# Main.net
KiCad netlist of a schematic drawn in Altium Designer
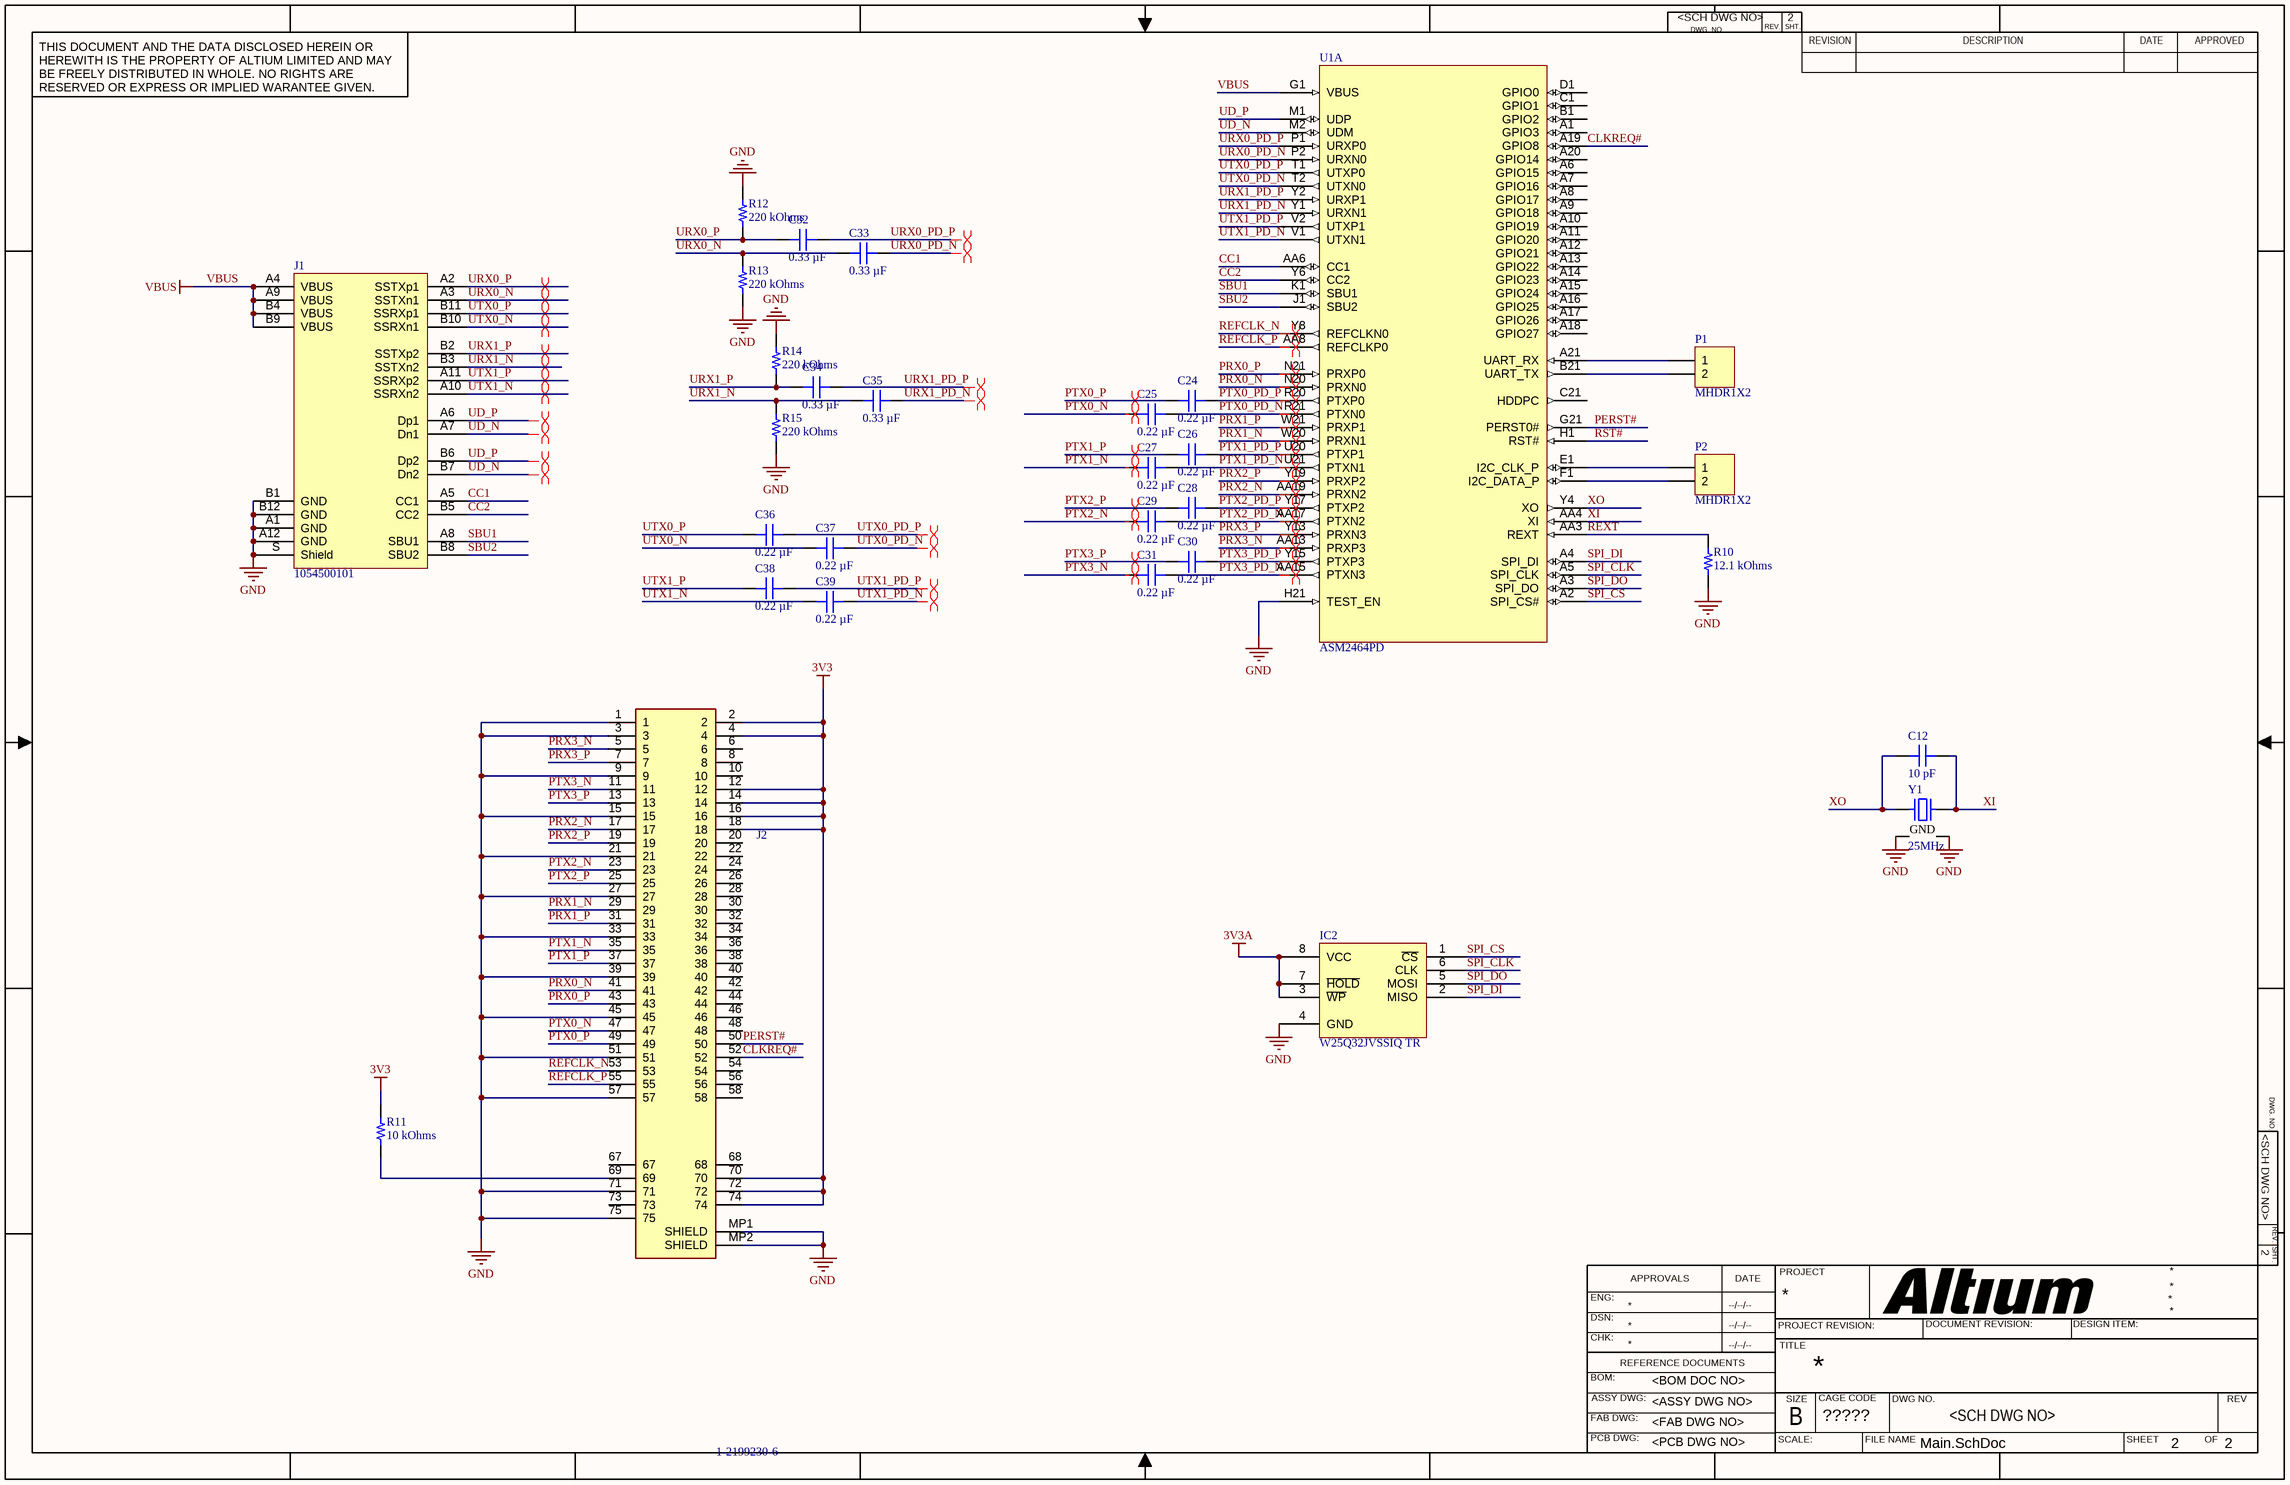
[diagram p0: Main.SchDoc]

(export (version "E")
  (design (tool "Eeschema 10.0.6"))
  (components
    (comp (ref "C12")
      (value "10 pF")
      (footprint "CAP 0603_1608")
      (description "CAP CER 10PF 200V C0G/NPO 0603")
      (fields (field (name "PART NUMBER") "CC0603JRNPOABN100") (field (name "MANUFACTURER") "Yageo"))
      (libsource (lib "Celestial Altium Library - altium_library") (part "Capacitor"))
    )
    (comp (ref "C24")
      (value "0.22 µF")
      (footprint "CAP 0402_1005")
      (description "CAP CER 0.22UF 35V X6S 0402")
      (fields
        (field (name "PART NUMBER") "GRM155C8YA224KE01J")
        (field (name "MANUFACTURER") "Murata Electronics")
      )
      (libsource (lib "Celestial Altium Library - altium_library") (part "Capacitor"))
    )
    (comp (ref "C25")
      (value "0.22 µF")
      (footprint "CAP 0402_1005")
      (description "CAP CER 0.22UF 35V X6S 0402")
      (fields
        (field (name "PART NUMBER") "GRM155C8YA224KE01J")
        (field (name "MANUFACTURER") "Murata Electronics")
      )
      (libsource (lib "Celestial Altium Library - altium_library") (part "Capacitor"))
    )
    (comp (ref "C26")
      (value "0.22 µF")
      (footprint "CAP 0402_1005")
      (description "CAP CER 0.22UF 35V X6S 0402")
      (fields
        (field (name "PART NUMBER") "GRM155C8YA224KE01J")
        (field (name "MANUFACTURER") "Murata Electronics")
      )
      (libsource (lib "Celestial Altium Library - altium_library") (part "Capacitor"))
    )
    (comp (ref "C27")
      (value "0.22 µF")
      (footprint "CAP 0402_1005")
      (description "CAP CER 0.22UF 35V X6S 0402")
      (fields
        (field (name "PART NUMBER") "GRM155C8YA224KE01J")
        (field (name "MANUFACTURER") "Murata Electronics")
      )
      (libsource (lib "Celestial Altium Library - altium_library") (part "Capacitor"))
    )
    (comp (ref "C28")
      (value "0.22 µF")
      (footprint "CAP 0402_1005")
      (description "CAP CER 0.22UF 35V X6S 0402")
      (fields
        (field (name "PART NUMBER") "GRM155C8YA224KE01J")
        (field (name "MANUFACTURER") "Murata Electronics")
      )
      (libsource (lib "Celestial Altium Library - altium_library") (part "Capacitor"))
    )
    (comp (ref "C29")
      (value "0.22 µF")
      (footprint "CAP 0402_1005")
      (description "CAP CER 0.22UF 35V X6S 0402")
      (fields
        (field (name "PART NUMBER") "GRM155C8YA224KE01J")
        (field (name "MANUFACTURER") "Murata Electronics")
      )
      (libsource (lib "Celestial Altium Library - altium_library") (part "Capacitor"))
    )
    (comp (ref "C30")
      (value "0.22 µF")
      (footprint "CAP 0402_1005")
      (description "CAP CER 0.22UF 35V X6S 0402")
      (fields
        (field (name "PART NUMBER") "GRM155C8YA224KE01J")
        (field (name "MANUFACTURER") "Murata Electronics")
      )
      (libsource (lib "Celestial Altium Library - altium_library") (part "Capacitor"))
    )
    (comp (ref "C31")
      (value "0.22 µF")
      (footprint "CAP 0402_1005")
      (description "CAP CER 0.22UF 35V X6S 0402")
      (fields
        (field (name "PART NUMBER") "GRM155C8YA224KE01J")
        (field (name "MANUFACTURER") "Murata Electronics")
      )
      (libsource (lib "Celestial Altium Library - altium_library") (part "Capacitor"))
    )
    (comp (ref "C32")
      (value "0.33 µF")
      (footprint "CAP 0201_0603")
      (description "CAP CER 0.33UF 6.3V X5R 0201")
      (fields
        (field (name "PART NUMBER") "GRM033R60J334ME90D")
        (field (name "MANUFACTURER") "Murata Electronics")
      )
      (libsource (lib "Celestial Altium Library - altium_library") (part "Capacitor"))
    )
    (comp (ref "C33")
      (value "0.33 µF")
      (footprint "CAP 0201_0603")
      (description "CAP CER 0.33UF 6.3V X5R 0201")
      (fields
        (field (name "PART NUMBER") "GRM033R60J334ME90D")
        (field (name "MANUFACTURER") "Murata Electronics")
      )
      (libsource (lib "Celestial Altium Library - altium_library") (part "Capacitor"))
    )
    (comp (ref "C34")
      (value "0.33 µF")
      (footprint "CAP 0201_0603")
      (description "CAP CER 0.33UF 6.3V X5R 0201")
      (fields
        (field (name "PART NUMBER") "GRM033R60J334ME90D")
        (field (name "MANUFACTURER") "Murata Electronics")
      )
      (libsource (lib "Celestial Altium Library - altium_library") (part "Capacitor"))
    )
    (comp (ref "C35")
      (value "0.33 µF")
      (footprint "CAP 0201_0603")
      (description "CAP CER 0.33UF 6.3V X5R 0201")
      (fields
        (field (name "PART NUMBER") "GRM033R60J334ME90D")
        (field (name "MANUFACTURER") "Murata Electronics")
      )
      (libsource (lib "Celestial Altium Library - altium_library") (part "Capacitor"))
    )
    (comp (ref "C36")
      (value "0.22 µF")
      (footprint "CAP 0201_0603")
      (description "CAP CER 0.22UF 25V X5R 0201")
      (fields
        (field (name "PART NUMBER") "GRM033R61E224KE01J")
        (field (name "MANUFACTURER") "Murata Electronics")
      )
      (libsource (lib "Celestial Altium Library - altium_library") (part "Capacitor"))
    )
    (comp (ref "C37")
      (value "0.22 µF")
      (footprint "CAP 0201_0603")
      (description "CAP CER 0.22UF 25V X5R 0201")
      (fields
        (field (name "PART NUMBER") "GRM033R61E224KE01J")
        (field (name "MANUFACTURER") "Murata Electronics")
      )
      (libsource (lib "Celestial Altium Library - altium_library") (part "Capacitor"))
    )
    (comp (ref "C38")
      (value "0.22 µF")
      (footprint "CAP 0201_0603")
      (description "CAP CER 0.22UF 25V X5R 0201")
      (fields
        (field (name "PART NUMBER") "GRM033R61E224KE01J")
        (field (name "MANUFACTURER") "Murata Electronics")
      )
      (libsource (lib "Celestial Altium Library - altium_library") (part "Capacitor"))
    )
    (comp (ref "C39")
      (value "0.22 µF")
      (footprint "CAP 0201_0603")
      (description "CAP CER 0.22UF 25V X5R 0201")
      (fields
        (field (name "PART NUMBER") "GRM033R61E224KE01J")
        (field (name "MANUFACTURER") "Murata Electronics")
      )
      (libsource (lib "Celestial Altium Library - altium_library") (part "Capacitor"))
    )
    (comp (ref "IC2")
      (value "W25Q32JVSSIQ TR")
      (footprint "WINBOND SOIC-8 208MIL WIDE")
      (description "IC FLASH 32M SPI 133MHZ 8SOIC")
      (fields (field (name "MANUFACTURER") "Winbond Electronics"))
      (libsource (lib "Celestial Altium Library - altium_library") (part "WINBOND FLASH SPI 8PIN"))
    )
    (comp (ref "J1")
      (value "1054500101")
      (footprint "Molex 1054500101")
      (description "CONN RCP USB3.1 TYPEC 24P SMD RA")
      (fields (field (name "MANUFACTURER") "Molex"))
      (libsource (lib "Celestial Altium Library - altium_library") (part "USB 3.0 Type C"))
    )
    (comp (ref "J2")
      (value "1-2199230-6")
      (footprint "121992306")
      (description "M.2 0.5PITCH 4.2H KEY M 30U AU")
      (fields (field (name "MF") "TE Connectivity") (field (name "DIGI-KEY_PART_NUMBER") "A118046TR-ND"))
      (libsource (lib "1-2199230-6") (part "1-2199230-6"))
    )
    (comp (ref "P1")
      (value "MHDR1X2")
      (footprint "MHDR1X2")
      (description "Header, 2-Pin")
      (fields (field (name "PUBLISHER") "Altium Limited"))
      (libsource (lib "Miscellaneous Connectors") (part "MHDR1X2"))
    )
    (comp (ref "P2")
      (value "MHDR1X2")
      (footprint "MHDR1X2")
      (description "Header, 2-Pin")
      (fields (field (name "PUBLISHER") "Altium Limited"))
      (libsource (lib "Miscellaneous Connectors") (part "MHDR1X2"))
    )
    (comp (ref "R10")
      (value "12.1 kOhms")
      (footprint "RES 0603_1608")
      (description "RES 12.1K OHM 0.1% 1/16W 0603")
      (fields
        (field (name "PART NUMBER") "RNCS0603BKE12K1")
        (field (name "MANUFACTURER") "Stackpole Electronics Inc")
      )
      (libsource (lib "Celestial Altium Library - altium_library") (part "Resistor"))
    )
    (comp (ref "R11")
      (value "10 kOhms")
      (footprint "RES 0805_2012")
      (description "RES SMD 10K OHM 1% 1/8W 0805")
      (fields (field (name "PART NUMBER") "CR0805-FX-1002ELF") (field (name "MANUFACTURER") "Bourns Inc."))
      (libsource (lib "Celestial Altium Library - altium_library") (part "Resistor"))
    )
    (comp (ref "R12")
      (value "220 kOhms")
      (footprint "RES 0201_0603")
      (description "RES SMD 220K OHM 1% 1/20W 0201")
      (fields
        (field (name "PART NUMBER") "ERJ-1GNF2203C")
        (field (name "MANUFACTURER") "Panasonic Electronic Components")
      )
      (libsource (lib "Celestial Altium Library - altium_library") (part "Resistor"))
    )
    (comp (ref "R13")
      (value "220 kOhms")
      (footprint "RES 0201_0603")
      (description "RES SMD 220K OHM 1% 1/20W 0201")
      (fields
        (field (name "PART NUMBER") "ERJ-1GNF2203C")
        (field (name "MANUFACTURER") "Panasonic Electronic Components")
      )
      (libsource (lib "Celestial Altium Library - altium_library") (part "Resistor"))
    )
    (comp (ref "R14")
      (value "220 kOhms")
      (footprint "RES 0201_0603")
      (description "RES SMD 220K OHM 1% 1/20W 0201")
      (fields
        (field (name "PART NUMBER") "ERJ-1GNF2203C")
        (field (name "MANUFACTURER") "Panasonic Electronic Components")
      )
      (libsource (lib "Celestial Altium Library - altium_library") (part "Resistor"))
    )
    (comp (ref "R15")
      (value "220 kOhms")
      (footprint "RES 0201_0603")
      (description "RES SMD 220K OHM 1% 1/20W 0201")
      (fields
        (field (name "PART NUMBER") "ERJ-1GNF2203C")
        (field (name "MANUFACTURER") "Panasonic Electronic Components")
      )
      (libsource (lib "Celestial Altium Library - altium_library") (part "Resistor"))
    )
    (comp (ref "U1")
      (value "ASM2464PD")
      (footprint "BGA273C46P21X21_1000X1000X98_2")
      (libsource (lib " JS") (part "ASM2464PD"))
    )
    (comp (ref "Y1")
      (value "25MHz")
      (footprint "ABRACON ABM8G")
      (description "CRYSTAL 25.0000MHZ 18PF SMD")
      (fields
        (field (name "PART NUMBER") "ABM8G-25.000MHZ-18-D2Y-T")
        (field (name "MANUFACTURER") "Abracon LLC")
      )
      (libsource (lib "Celestial Altium Library - altium_library") (part "Abracon Crystal ABM8G"))
    )
  )
  (nets
    (net (code "1") (name "/CC1") (class "Default")
      (node (ref "J1") (pin "A5") (pinfunction "CC1_A5") (pintype "passive"))
      (node (ref "U1") (pin "AA6") (pinfunction "CC1_AA6") (pintype "bidirectional"))
    )
    (net (code "2") (name "/CC2") (class "Default")
      (node (ref "J1") (pin "B5") (pinfunction "CC2_B5") (pintype "passive"))
      (node (ref "U1") (pin "Y6") (pinfunction "CC2_Y6") (pintype "bidirectional"))
    )
    (net (code "3") (name "/CLKREQ#") (class "Default")
      (node (ref "J2") (pin "52") (pinfunction "52_52") (pintype "passive"))
      (node (ref "U1") (pin "A19") (pinfunction "GPIO8_A19") (pintype "bidirectional"))
    )
    (net (code "4") (name "/PERST#") (class "Default")
      (node (ref "J2") (pin "50") (pinfunction "50_50") (pintype "passive"))
      (node (ref "U1") (pin "G21") (pinfunction "PERST0#_G21") (pintype "output"))
    )
    (net (code "5") (name "/PRX0_N") (class "Default")
      (node (ref "J2") (pin "41") (pinfunction "41_41") (pintype "passive"))
      (node (ref "U1") (pin "N20") (pinfunction "PRXN0_N20") (pintype "input"))
    )
    (net (code "6") (name "/PRX0_P") (class "Default")
      (node (ref "J2") (pin "43") (pinfunction "43_43") (pintype "passive"))
      (node (ref "U1") (pin "N21") (pinfunction "PRXP0_N21") (pintype "input"))
    )
    (net (code "7") (name "/PRX1_N") (class "Default")
      (node (ref "J2") (pin "29") (pinfunction "29_29") (pintype "passive"))
      (node (ref "U1") (pin "W20") (pinfunction "PRXN1_W20") (pintype "input"))
    )
    (net (code "8") (name "/PRX1_P") (class "Default")
      (node (ref "J2") (pin "31") (pinfunction "31_31") (pintype "passive"))
      (node (ref "U1") (pin "W21") (pinfunction "PRXP1_W21") (pintype "input"))
    )
    (net (code "9") (name "/PRX2_N") (class "Default")
      (node (ref "J2") (pin "17") (pinfunction "17_17") (pintype "passive"))
      (node (ref "U1") (pin "AA19") (pinfunction "PRXN2_AA19") (pintype "input"))
    )
    (net (code "10") (name "/PRX2_P") (class "Default")
      (node (ref "J2") (pin "19") (pinfunction "19_19") (pintype "passive"))
      (node (ref "U1") (pin "Y19") (pinfunction "PRXP2_Y19") (pintype "input"))
    )
    (net (code "11") (name "/PRX3_N") (class "Default")
      (node (ref "J2") (pin "5") (pinfunction "5_5") (pintype "passive"))
      (node (ref "U1") (pin "AA13") (pinfunction "PRXP3_AA13") (pintype "input"))
    )
    (net (code "12") (name "/PRX3_P") (class "Default")
      (node (ref "J2") (pin "7") (pinfunction "7_7") (pintype "passive"))
      (node (ref "U1") (pin "Y13") (pinfunction "PRXN3_Y13") (pintype "input"))
    )
    (net (code "13") (name "/PTX0_N") (class "Default")
      (node (ref "C25") (pin "1") (pinfunction "1_1") (pintype "passive"))
      (node (ref "J2") (pin "47") (pinfunction "47_47") (pintype "passive"))
    )
    (net (code "14") (name "/PTX0_P") (class "Default")
      (node (ref "C24") (pin "1") (pinfunction "1_1") (pintype "passive"))
      (node (ref "J2") (pin "49") (pinfunction "49_49") (pintype "passive"))
    )
    (net (code "15") (name "/PTX0_PD_N") (class "Default")
      (node (ref "C25") (pin "2") (pinfunction "2_2") (pintype "passive"))
      (node (ref "U1") (pin "R21") (pinfunction "PTXN0_R21") (pintype "output"))
    )
    (net (code "16") (name "/PTX0_PD_P") (class "Default")
      (node (ref "C24") (pin "2") (pinfunction "2_2") (pintype "passive"))
      (node (ref "U1") (pin "R20") (pinfunction "PTXP0_R20") (pintype "output"))
    )
    (net (code "17") (name "/PTX1_N") (class "Default")
      (node (ref "C27") (pin "1") (pinfunction "1_1") (pintype "passive"))
      (node (ref "J2") (pin "35") (pinfunction "35_35") (pintype "passive"))
    )
    (net (code "18") (name "/PTX1_P") (class "Default")
      (node (ref "C26") (pin "1") (pinfunction "1_1") (pintype "passive"))
      (node (ref "J2") (pin "37") (pinfunction "37_37") (pintype "passive"))
    )
    (net (code "19") (name "/PTX1_PD_N") (class "Default")
      (node (ref "C27") (pin "2") (pinfunction "2_2") (pintype "passive"))
      (node (ref "U1") (pin "U21") (pinfunction "PTXN1_U21") (pintype "output"))
    )
    (net (code "20") (name "/PTX1_PD_P") (class "Default")
      (node (ref "C26") (pin "2") (pinfunction "2_2") (pintype "passive"))
      (node (ref "U1") (pin "U20") (pinfunction "PTXP1_U20") (pintype "output"))
    )
    (net (code "21") (name "/PTX2_N") (class "Default")
      (node (ref "C29") (pin "1") (pinfunction "1_1") (pintype "passive"))
      (node (ref "J2") (pin "23") (pinfunction "23_23") (pintype "passive"))
    )
    (net (code "22") (name "/PTX2_P") (class "Default")
      (node (ref "C28") (pin "1") (pinfunction "1_1") (pintype "passive"))
      (node (ref "J2") (pin "25") (pinfunction "25_25") (pintype "passive"))
    )
    (net (code "23") (name "/PTX2_PD_N") (class "Default")
      (node (ref "C29") (pin "2") (pinfunction "2_2") (pintype "passive"))
      (node (ref "U1") (pin "AA17") (pinfunction "PTXN2_AA17") (pintype "output"))
    )
    (net (code "24") (name "/PTX2_PD_P") (class "Default")
      (node (ref "C28") (pin "2") (pinfunction "2_2") (pintype "passive"))
      (node (ref "U1") (pin "Y17") (pinfunction "PTXP2_Y17") (pintype "output"))
    )
    (net (code "25") (name "/PTX3_N") (class "Default")
      (node (ref "C31") (pin "1") (pinfunction "1_1") (pintype "passive"))
      (node (ref "J2") (pin "11") (pinfunction "11_11") (pintype "passive"))
    )
    (net (code "26") (name "/PTX3_P") (class "Default")
      (node (ref "C30") (pin "1") (pinfunction "1_1") (pintype "passive"))
      (node (ref "J2") (pin "13") (pinfunction "13_13") (pintype "passive"))
    )
    (net (code "27") (name "/PTX3_PD_N") (class "Default")
      (node (ref "C31") (pin "2") (pinfunction "2_2") (pintype "passive"))
      (node (ref "U1") (pin "AA15") (pinfunction "PTXN3_AA15") (pintype "output"))
    )
    (net (code "28") (name "/PTX3_PD_P") (class "Default")
      (node (ref "C30") (pin "2") (pinfunction "2_2") (pintype "passive"))
      (node (ref "U1") (pin "Y15") (pinfunction "PTXP3_Y15") (pintype "output"))
    )
    (net (code "29") (name "/REFCLK_N") (class "Default")
      (node (ref "J2") (pin "53") (pinfunction "53_53") (pintype "passive"))
      (node (ref "U1") (pin "Y8") (pinfunction "REFCLKN0_Y8") (pintype "output"))
    )
    (net (code "30") (name "/REFCLK_P") (class "Default")
      (node (ref "J2") (pin "55") (pinfunction "55_55") (pintype "passive"))
      (node (ref "U1") (pin "AA8") (pinfunction "REFCLKP0_AA8") (pintype "output"))
    )
    (net (code "31") (name "/REXT") (class "Default")
      (node (ref "R10") (pin "2") (pinfunction "2_2") (pintype "passive"))
      (node (ref "U1") (pin "AA3") (pinfunction "REXT_AA3") (pintype "input"))
    )
    (net (code "32") (name "/RST#") (class "Default")
      (node (ref "U1") (pin "H1") (pinfunction "RST#_H1") (pintype "input"))
    )
    (net (code "33") (name "/SBU1") (class "Default")
      (node (ref "J1") (pin "A8") (pinfunction "SBU1_A8") (pintype "passive"))
      (node (ref "U1") (pin "K1") (pinfunction "SBU1_K1") (pintype "bidirectional"))
    )
    (net (code "34") (name "/SBU2") (class "Default")
      (node (ref "J1") (pin "B8") (pinfunction "SBU2_B8") (pintype "passive"))
      (node (ref "U1") (pin "J1") (pinfunction "SBU2_J1") (pintype "bidirectional"))
    )
    (net (code "35") (name "/SPI_CLK") (class "Default")
      (node (ref "IC2") (pin "6") (pinfunction "CLK_6") (pintype "passive"))
      (node (ref "U1") (pin "A5") (pinfunction "SPI_CLK_A5") (pintype "bidirectional"))
    )
    (net (code "36") (name "/SPI_CS") (class "Default")
      (node (ref "IC2") (pin "1") (pinfunction "~{CS}_1") (pintype "passive"))
      (node (ref "U1") (pin "A2") (pinfunction "SPI_CS#_A2") (pintype "bidirectional"))
    )
    (net (code "37") (name "/SPI_DI") (class "Default")
      (node (ref "IC2") (pin "2") (pinfunction "MISO_2") (pintype "passive"))
      (node (ref "U1") (pin "A4") (pinfunction "SPI_DI_A4") (pintype "bidirectional"))
    )
    (net (code "38") (name "/SPI_DO") (class "Default")
      (node (ref "IC2") (pin "5") (pinfunction "MOSI_5") (pintype "passive"))
      (node (ref "U1") (pin "A3") (pinfunction "SPI_DO_A3") (pintype "bidirectional"))
    )
    (net (code "39") (name "/UD_N") (class "Default")
      (node (ref "J1") (pin "A7") (pinfunction "Dn1_A7") (pintype "passive"))
      (node (ref "J1") (pin "B7") (pinfunction "Dn2_B7") (pintype "passive"))
      (node (ref "U1") (pin "M2") (pinfunction "UDM_M2") (pintype "bidirectional"))
    )
    (net (code "40") (name "/UD_P") (class "Default")
      (node (ref "J1") (pin "A6") (pinfunction "Dp1_A6") (pintype "passive"))
      (node (ref "J1") (pin "B6") (pinfunction "Dp2_B6") (pintype "passive"))
      (node (ref "U1") (pin "M1") (pinfunction "UDP_M1") (pintype "bidirectional"))
    )
    (net (code "41") (name "/URX0_N") (class "Default")
      (node (ref "C33") (pin "1") (pinfunction "1_1") (pintype "passive"))
      (node (ref "J1") (pin "A3") (pinfunction "SSTXn1_A3") (pintype "passive"))
      (node (ref "R13") (pin "2") (pinfunction "2_2") (pintype "passive"))
    )
    (net (code "42") (name "/URX0_P") (class "Default")
      (node (ref "C32") (pin "1") (pinfunction "1_1") (pintype "passive"))
      (node (ref "J1") (pin "A2") (pinfunction "SSTXp1_A2") (pintype "passive"))
      (node (ref "R12") (pin "1") (pinfunction "1_1") (pintype "passive"))
    )
    (net (code "43") (name "/URX0_PD_N") (class "Default")
      (node (ref "C33") (pin "2") (pinfunction "2_2") (pintype "passive"))
      (node (ref "U1") (pin "P2") (pinfunction "URXN0_P2") (pintype "input"))
    )
    (net (code "44") (name "/URX0_PD_P") (class "Default")
      (node (ref "C32") (pin "2") (pinfunction "2_2") (pintype "passive"))
      (node (ref "U1") (pin "P1") (pinfunction "URXP0_P1") (pintype "input"))
    )
    (net (code "45") (name "/URX1_N") (class "Default")
      (node (ref "C35") (pin "1") (pinfunction "1_1") (pintype "passive"))
      (node (ref "J1") (pin "B3") (pinfunction "SSTXn2_B3") (pintype "passive"))
      (node (ref "R15") (pin "1") (pinfunction "1_1") (pintype "passive"))
    )
    (net (code "46") (name "/URX1_P") (class "Default")
      (node (ref "C34") (pin "1") (pinfunction "1_1") (pintype "passive"))
      (node (ref "J1") (pin "B2") (pinfunction "SSTXp2_B2") (pintype "passive"))
      (node (ref "R14") (pin "1") (pinfunction "1_1") (pintype "passive"))
    )
    (net (code "47") (name "/URX1_PD_N") (class "Default")
      (node (ref "C35") (pin "2") (pinfunction "2_2") (pintype "passive"))
      (node (ref "U1") (pin "Y1") (pinfunction "URXN1_Y1") (pintype "input"))
    )
    (net (code "48") (name "/URX1_PD_P") (class "Default")
      (node (ref "C34") (pin "2") (pinfunction "2_2") (pintype "passive"))
      (node (ref "U1") (pin "Y2") (pinfunction "URXP1_Y2") (pintype "input"))
    )
    (net (code "49") (name "/UTX0_N") (class "Default")
      (node (ref "C37") (pin "1") (pinfunction "1_1") (pintype "passive"))
      (node (ref "J1") (pin "B10") (pinfunction "SSRXn1_B10") (pintype "passive"))
    )
    (net (code "50") (name "/UTX0_P") (class "Default")
      (node (ref "C36") (pin "1") (pinfunction "1_1") (pintype "passive"))
      (node (ref "J1") (pin "B11") (pinfunction "SSRXp1_B11") (pintype "passive"))
    )
    (net (code "51") (name "/UTX0_PD_N") (class "Default")
      (node (ref "C37") (pin "2") (pinfunction "2_2") (pintype "passive"))
      (node (ref "U1") (pin "T2") (pinfunction "UTXN0_T2") (pintype "output"))
    )
    (net (code "52") (name "/UTX0_PD_P") (class "Default")
      (node (ref "C36") (pin "2") (pinfunction "2_2") (pintype "passive"))
      (node (ref "U1") (pin "T1") (pinfunction "UTXP0_T1") (pintype "output"))
    )
    (net (code "53") (name "/UTX1_N") (class "Default")
      (node (ref "C39") (pin "1") (pinfunction "1_1") (pintype "passive"))
      (node (ref "J1") (pin "A10") (pinfunction "SSRXn2_A10") (pintype "passive"))
    )
    (net (code "54") (name "/UTX1_P") (class "Default")
      (node (ref "C38") (pin "1") (pinfunction "1_1") (pintype "passive"))
      (node (ref "J1") (pin "A11") (pinfunction "SSRXp2_A11") (pintype "passive"))
    )
    (net (code "55") (name "/UTX1_PD_N") (class "Default")
      (node (ref "C39") (pin "2") (pinfunction "2_2") (pintype "passive"))
      (node (ref "U1") (pin "V1") (pinfunction "UTXN1_V1") (pintype "output"))
    )
    (net (code "56") (name "/UTX1_PD_P") (class "Default")
      (node (ref "C38") (pin "2") (pinfunction "2_2") (pintype "passive"))
      (node (ref "U1") (pin "V2") (pinfunction "UTXP1_V2") (pintype "output"))
    )
    (net (code "57") (name "/XI") (class "Default")
      (node (ref "C12") (pin "2") (pinfunction "2_2") (pintype "passive"))
      (node (ref "U1") (pin "AA4") (pinfunction "XI_AA4") (pintype "input"))
      (node (ref "Y1") (pin "3") (pinfunction "3_3") (pintype "passive"))
    )
    (net (code "58") (name "/XO") (class "Default")
      (node (ref "C12") (pin "1") (pinfunction "1_1") (pintype "passive"))
      (node (ref "U1") (pin "Y4") (pinfunction "XO_Y4") (pintype "output"))
      (node (ref "Y1") (pin "1") (pinfunction "1_1") (pintype "passive"))
    )
    (net (code "59") (name "3V3") (class "Default")
      (node (ref "J2") (pin "12") (pinfunction "12_12") (pintype "passive"))
      (node (ref "J2") (pin "14") (pinfunction "14_14") (pintype "passive"))
      (node (ref "J2") (pin "16") (pinfunction "16_16") (pintype "passive"))
      (node (ref "J2") (pin "18") (pinfunction "18_18") (pintype "passive"))
      (node (ref "J2") (pin "2") (pinfunction "2_2") (pintype "passive"))
      (node (ref "J2") (pin "4") (pinfunction "4_4") (pintype "passive"))
      (node (ref "J2") (pin "70") (pinfunction "70_70") (pintype "passive"))
      (node (ref "J2") (pin "72") (pinfunction "72_72") (pintype "passive"))
      (node (ref "J2") (pin "74") (pinfunction "74_74") (pintype "passive"))
      (node (ref "R11") (pin "2") (pinfunction "2_2") (pintype "passive"))
    )
    (net (code "60") (name "3V3A") (class "Default")
      (node (ref "IC2") (pin "3") (pinfunction "~{WP}_3") (pintype "passive"))
      (node (ref "IC2") (pin "7") (pinfunction "~{HOLD}_7") (pintype "passive"))
      (node (ref "IC2") (pin "8") (pinfunction "VCC_8") (pintype "passive"))
    )
    (net (code "61") (name "GND") (class "Default")
      (node (ref "IC2") (pin "4") (pinfunction "GND_4") (pintype "passive"))
      (node (ref "J1") (pin "A1") (pinfunction "GND_A1") (pintype "passive"))
      (node (ref "J1") (pin "A12") (pinfunction "GND_A12") (pintype "passive"))
      (node (ref "J1") (pin "B1") (pinfunction "GND_B1") (pintype "passive"))
      (node (ref "J1") (pin "B12") (pinfunction "GND_B12") (pintype "passive"))
      (node (ref "J1") (pin "S") (pinfunction "Shield_S") (pintype "passive"))
      (node (ref "J2") (pin "1") (pinfunction "1_1") (pintype "passive"))
      (node (ref "J2") (pin "15") (pinfunction "15_15") (pintype "passive"))
      (node (ref "J2") (pin "21") (pinfunction "21_21") (pintype "passive"))
      (node (ref "J2") (pin "27") (pinfunction "27_27") (pintype "passive"))
      (node (ref "J2") (pin "3") (pinfunction "3_3") (pintype "passive"))
      (node (ref "J2") (pin "33") (pinfunction "33_33") (pintype "passive"))
      (node (ref "J2") (pin "39") (pinfunction "39_39") (pintype "passive"))
      (node (ref "J2") (pin "45") (pinfunction "45_45") (pintype "passive"))
      (node (ref "J2") (pin "51") (pinfunction "51_51") (pintype "passive"))
      (node (ref "J2") (pin "57") (pinfunction "57_57") (pintype "passive"))
      (node (ref "J2") (pin "71") (pinfunction "71_71") (pintype "passive"))
      (node (ref "J2") (pin "75") (pinfunction "75_75") (pintype "passive"))
      (node (ref "J2") (pin "9") (pinfunction "9_9") (pintype "passive"))
      (node (ref "J2") (pin "MP1") (pinfunction "SHIELD_MP1") (pintype "passive"))
      (node (ref "J2") (pin "MP2") (pinfunction "SHIELD_MP2") (pintype "passive"))
      (node (ref "R10") (pin "1") (pinfunction "1_1") (pintype "passive"))
      (node (ref "R12") (pin "2") (pinfunction "2_2") (pintype "passive"))
      (node (ref "R13") (pin "1") (pinfunction "1_1") (pintype "passive"))
      (node (ref "R14") (pin "2") (pinfunction "2_2") (pintype "passive"))
      (node (ref "R15") (pin "2") (pinfunction "2_2") (pintype "passive"))
      (node (ref "U1") (pin "H21") (pinfunction "TEST_EN_H21") (pintype "input"))
      (node (ref "Y1") (pin "2") (pinfunction "GND_2") (pintype "passive"))
      (node (ref "Y1") (pin "4") (pinfunction "GND_4") (pintype "passive"))
    )
    (net (code "62") (name "Net-(J2-Pad69)") (class "Default")
      (node (ref "J2") (pin "69") (pinfunction "69_69") (pintype "passive"))
      (node (ref "R11") (pin "1") (pinfunction "1_1") (pintype "passive"))
    )
    (net (code "63") (name "Net-(U1A-I2C_CLK_P)") (class "Default")
      (node (ref "P2") (pin "1") (pinfunction "1_1") (pintype "passive"))
      (node (ref "U1") (pin "E1") (pinfunction "I2C_CLK_P_E1") (pintype "bidirectional"))
    )
    (net (code "64") (name "Net-(U1A-I2C_DATA_P)") (class "Default")
      (node (ref "P2") (pin "2") (pinfunction "2_2") (pintype "passive"))
      (node (ref "U1") (pin "F1") (pinfunction "I2C_DATA_P_F1") (pintype "bidirectional"))
    )
    (net (code "65") (name "Net-(U1A-UART_RX)") (class "Default")
      (node (ref "P1") (pin "1") (pinfunction "1_1") (pintype "passive"))
      (node (ref "U1") (pin "A21") (pinfunction "UART_RX_A21") (pintype "input"))
    )
    (net (code "66") (name "Net-(U1A-UART_TX)") (class "Default")
      (node (ref "P1") (pin "2") (pinfunction "2_2") (pintype "passive"))
      (node (ref "U1") (pin "B21") (pinfunction "UART_TX_B21") (pintype "output"))
    )
    (net (code "67") (name "VBUS") (class "Default")
      (node (ref "J1") (pin "A4") (pinfunction "VBUS_A4") (pintype "passive"))
      (node (ref "J1") (pin "A9") (pinfunction "VBUS_A9") (pintype "passive"))
      (node (ref "J1") (pin "B4") (pinfunction "VBUS_B4") (pintype "passive"))
      (node (ref "J1") (pin "B9") (pinfunction "VBUS_B9") (pintype "passive"))
      (node (ref "U1") (pin "G1") (pinfunction "VBUS_G1") (pintype "input"))
    )
    (net (code "68") (name "unconnected-(J2-Pad6)") (class "Default")
      (node (ref "J2") (pin "6") (pinfunction "6_6") (pintype "passive"))
    )
    (net (code "69") (name "unconnected-(J2-Pad8)") (class "Default")
      (node (ref "J2") (pin "8") (pinfunction "8_8") (pintype "passive"))
    )
    (net (code "70") (name "unconnected-(J2-Pad10)") (class "Default")
      (node (ref "J2") (pin "10") (pinfunction "10_10") (pintype "passive"))
    )
    (net (code "71") (name "unconnected-(J2-Pad20)") (class "Default")
      (node (ref "J2") (pin "20") (pinfunction "20_20") (pintype "passive"))
    )
    (net (code "72") (name "unconnected-(J2-Pad22)") (class "Default")
      (node (ref "J2") (pin "22") (pinfunction "22_22") (pintype "passive"))
    )
    (net (code "73") (name "unconnected-(J2-Pad24)") (class "Default")
      (node (ref "J2") (pin "24") (pinfunction "24_24") (pintype "passive"))
    )
    (net (code "74") (name "unconnected-(J2-Pad26)") (class "Default")
      (node (ref "J2") (pin "26") (pinfunction "26_26") (pintype "passive"))
    )
    (net (code "75") (name "unconnected-(J2-Pad28)") (class "Default")
      (node (ref "J2") (pin "28") (pinfunction "28_28") (pintype "passive"))
    )
    (net (code "76") (name "unconnected-(J2-Pad30)") (class "Default")
      (node (ref "J2") (pin "30") (pinfunction "30_30") (pintype "passive"))
    )
    (net (code "77") (name "unconnected-(J2-Pad32)") (class "Default")
      (node (ref "J2") (pin "32") (pinfunction "32_32") (pintype "passive"))
    )
    (net (code "78") (name "unconnected-(J2-Pad34)") (class "Default")
      (node (ref "J2") (pin "34") (pinfunction "34_34") (pintype "passive"))
    )
    (net (code "79") (name "unconnected-(J2-Pad36)") (class "Default")
      (node (ref "J2") (pin "36") (pinfunction "36_36") (pintype "passive"))
    )
    (net (code "80") (name "unconnected-(J2-Pad38)") (class "Default")
      (node (ref "J2") (pin "38") (pinfunction "38_38") (pintype "passive"))
    )
    (net (code "81") (name "unconnected-(J2-Pad40)") (class "Default")
      (node (ref "J2") (pin "40") (pinfunction "40_40") (pintype "passive"))
    )
    (net (code "82") (name "unconnected-(J2-Pad42)") (class "Default")
      (node (ref "J2") (pin "42") (pinfunction "42_42") (pintype "passive"))
    )
    (net (code "83") (name "unconnected-(J2-Pad44)") (class "Default")
      (node (ref "J2") (pin "44") (pinfunction "44_44") (pintype "passive"))
    )
    (net (code "84") (name "unconnected-(J2-Pad46)") (class "Default")
      (node (ref "J2") (pin "46") (pinfunction "46_46") (pintype "passive"))
    )
    (net (code "85") (name "unconnected-(J2-Pad48)") (class "Default")
      (node (ref "J2") (pin "48") (pinfunction "48_48") (pintype "passive"))
    )
    (net (code "86") (name "unconnected-(J2-Pad54)") (class "Default")
      (node (ref "J2") (pin "54") (pinfunction "54_54") (pintype "passive"))
    )
    (net (code "87") (name "unconnected-(J2-Pad56)") (class "Default")
      (node (ref "J2") (pin "56") (pinfunction "56_56") (pintype "passive"))
    )
    (net (code "88") (name "unconnected-(J2-Pad58)") (class "Default")
      (node (ref "J2") (pin "58") (pinfunction "58_58") (pintype "passive"))
    )
    (net (code "89") (name "unconnected-(J2-Pad67)") (class "Default")
      (node (ref "J2") (pin "67") (pinfunction "67_67") (pintype "passive"))
    )
    (net (code "90") (name "unconnected-(J2-Pad68)") (class "Default")
      (node (ref "J2") (pin "68") (pinfunction "68_68") (pintype "passive"))
    )
    (net (code "91") (name "unconnected-(J2-Pad73)") (class "Default")
      (node (ref "J2") (pin "73") (pinfunction "73_73") (pintype "passive"))
    )
    (net (code "92") (name "unconnected-(U1A-GPIO0-PadD1)") (class "Default")
      (node (ref "U1") (pin "D1") (pinfunction "GPIO0_D1") (pintype "bidirectional"))
    )
    (net (code "93") (name "unconnected-(U1A-GPIO1-PadC1)") (class "Default")
      (node (ref "U1") (pin "C1") (pinfunction "GPIO1_C1") (pintype "bidirectional"))
    )
    (net (code "94") (name "unconnected-(U1A-GPIO2-PadB1)") (class "Default")
      (node (ref "U1") (pin "B1") (pinfunction "GPIO2_B1") (pintype "bidirectional"))
    )
    (net (code "95") (name "unconnected-(U1A-GPIO3-PadA1)") (class "Default")
      (node (ref "U1") (pin "A1") (pinfunction "GPIO3_A1") (pintype "bidirectional"))
    )
    (net (code "96") (name "unconnected-(U1A-GPIO14-PadA20)") (class "Default")
      (node (ref "U1") (pin "A20") (pinfunction "GPIO14_A20") (pintype "bidirectional"))
    )
    (net (code "97") (name "unconnected-(U1A-GPIO15-PadA6)") (class "Default")
      (node (ref "U1") (pin "A6") (pinfunction "GPIO15_A6") (pintype "bidirectional"))
    )
    (net (code "98") (name "unconnected-(U1A-GPIO16-PadA7)") (class "Default")
      (node (ref "U1") (pin "A7") (pinfunction "GPIO16_A7") (pintype "bidirectional"))
    )
    (net (code "99") (name "unconnected-(U1A-GPIO17-PadA8)") (class "Default")
      (node (ref "U1") (pin "A8") (pinfunction "GPIO17_A8") (pintype "bidirectional"))
    )
    (net (code "100") (name "unconnected-(U1A-GPIO18-PadA9)") (class "Default")
      (node (ref "U1") (pin "A9") (pinfunction "GPIO18_A9") (pintype "bidirectional"))
    )
    (net (code "101") (name "unconnected-(U1A-GPIO19-PadA10)") (class "Default")
      (node (ref "U1") (pin "A10") (pinfunction "GPIO19_A10") (pintype "bidirectional"))
    )
    (net (code "102") (name "unconnected-(U1A-GPIO20-PadA11)") (class "Default")
      (node (ref "U1") (pin "A11") (pinfunction "GPIO20_A11") (pintype "bidirectional"))
    )
    (net (code "103") (name "unconnected-(U1A-GPIO21-PadA12)") (class "Default")
      (node (ref "U1") (pin "A12") (pinfunction "GPIO21_A12") (pintype "bidirectional"))
    )
    (net (code "104") (name "unconnected-(U1A-GPIO22-PadA13)") (class "Default")
      (node (ref "U1") (pin "A13") (pinfunction "GPIO22_A13") (pintype "bidirectional"))
    )
    (net (code "105") (name "unconnected-(U1A-GPIO23-PadA14)") (class "Default")
      (node (ref "U1") (pin "A14") (pinfunction "GPIO23_A14") (pintype "bidirectional"))
    )
    (net (code "106") (name "unconnected-(U1A-GPIO24-PadA15)") (class "Default")
      (node (ref "U1") (pin "A15") (pinfunction "GPIO24_A15") (pintype "bidirectional"))
    )
    (net (code "107") (name "unconnected-(U1A-GPIO25-PadA16)") (class "Default")
      (node (ref "U1") (pin "A16") (pinfunction "GPIO25_A16") (pintype "bidirectional"))
    )
    (net (code "108") (name "unconnected-(U1A-GPIO26-PadA17)") (class "Default")
      (node (ref "U1") (pin "A17") (pinfunction "GPIO26_A17") (pintype "bidirectional"))
    )
    (net (code "109") (name "unconnected-(U1A-GPIO27-PadA18)") (class "Default")
      (node (ref "U1") (pin "A18") (pinfunction "GPIO27_A18") (pintype "bidirectional"))
    )
    (net (code "110") (name "unconnected-(U1A-HDDPC-PadC21)") (class "Default")
      (node (ref "U1") (pin "C21") (pinfunction "HDDPC_C21") (pintype "output"))
    )
  )
)
